# STeaMi-FP13-Port_Specifique.net
KiCad netlist of a schematic drawn in Altium Designer
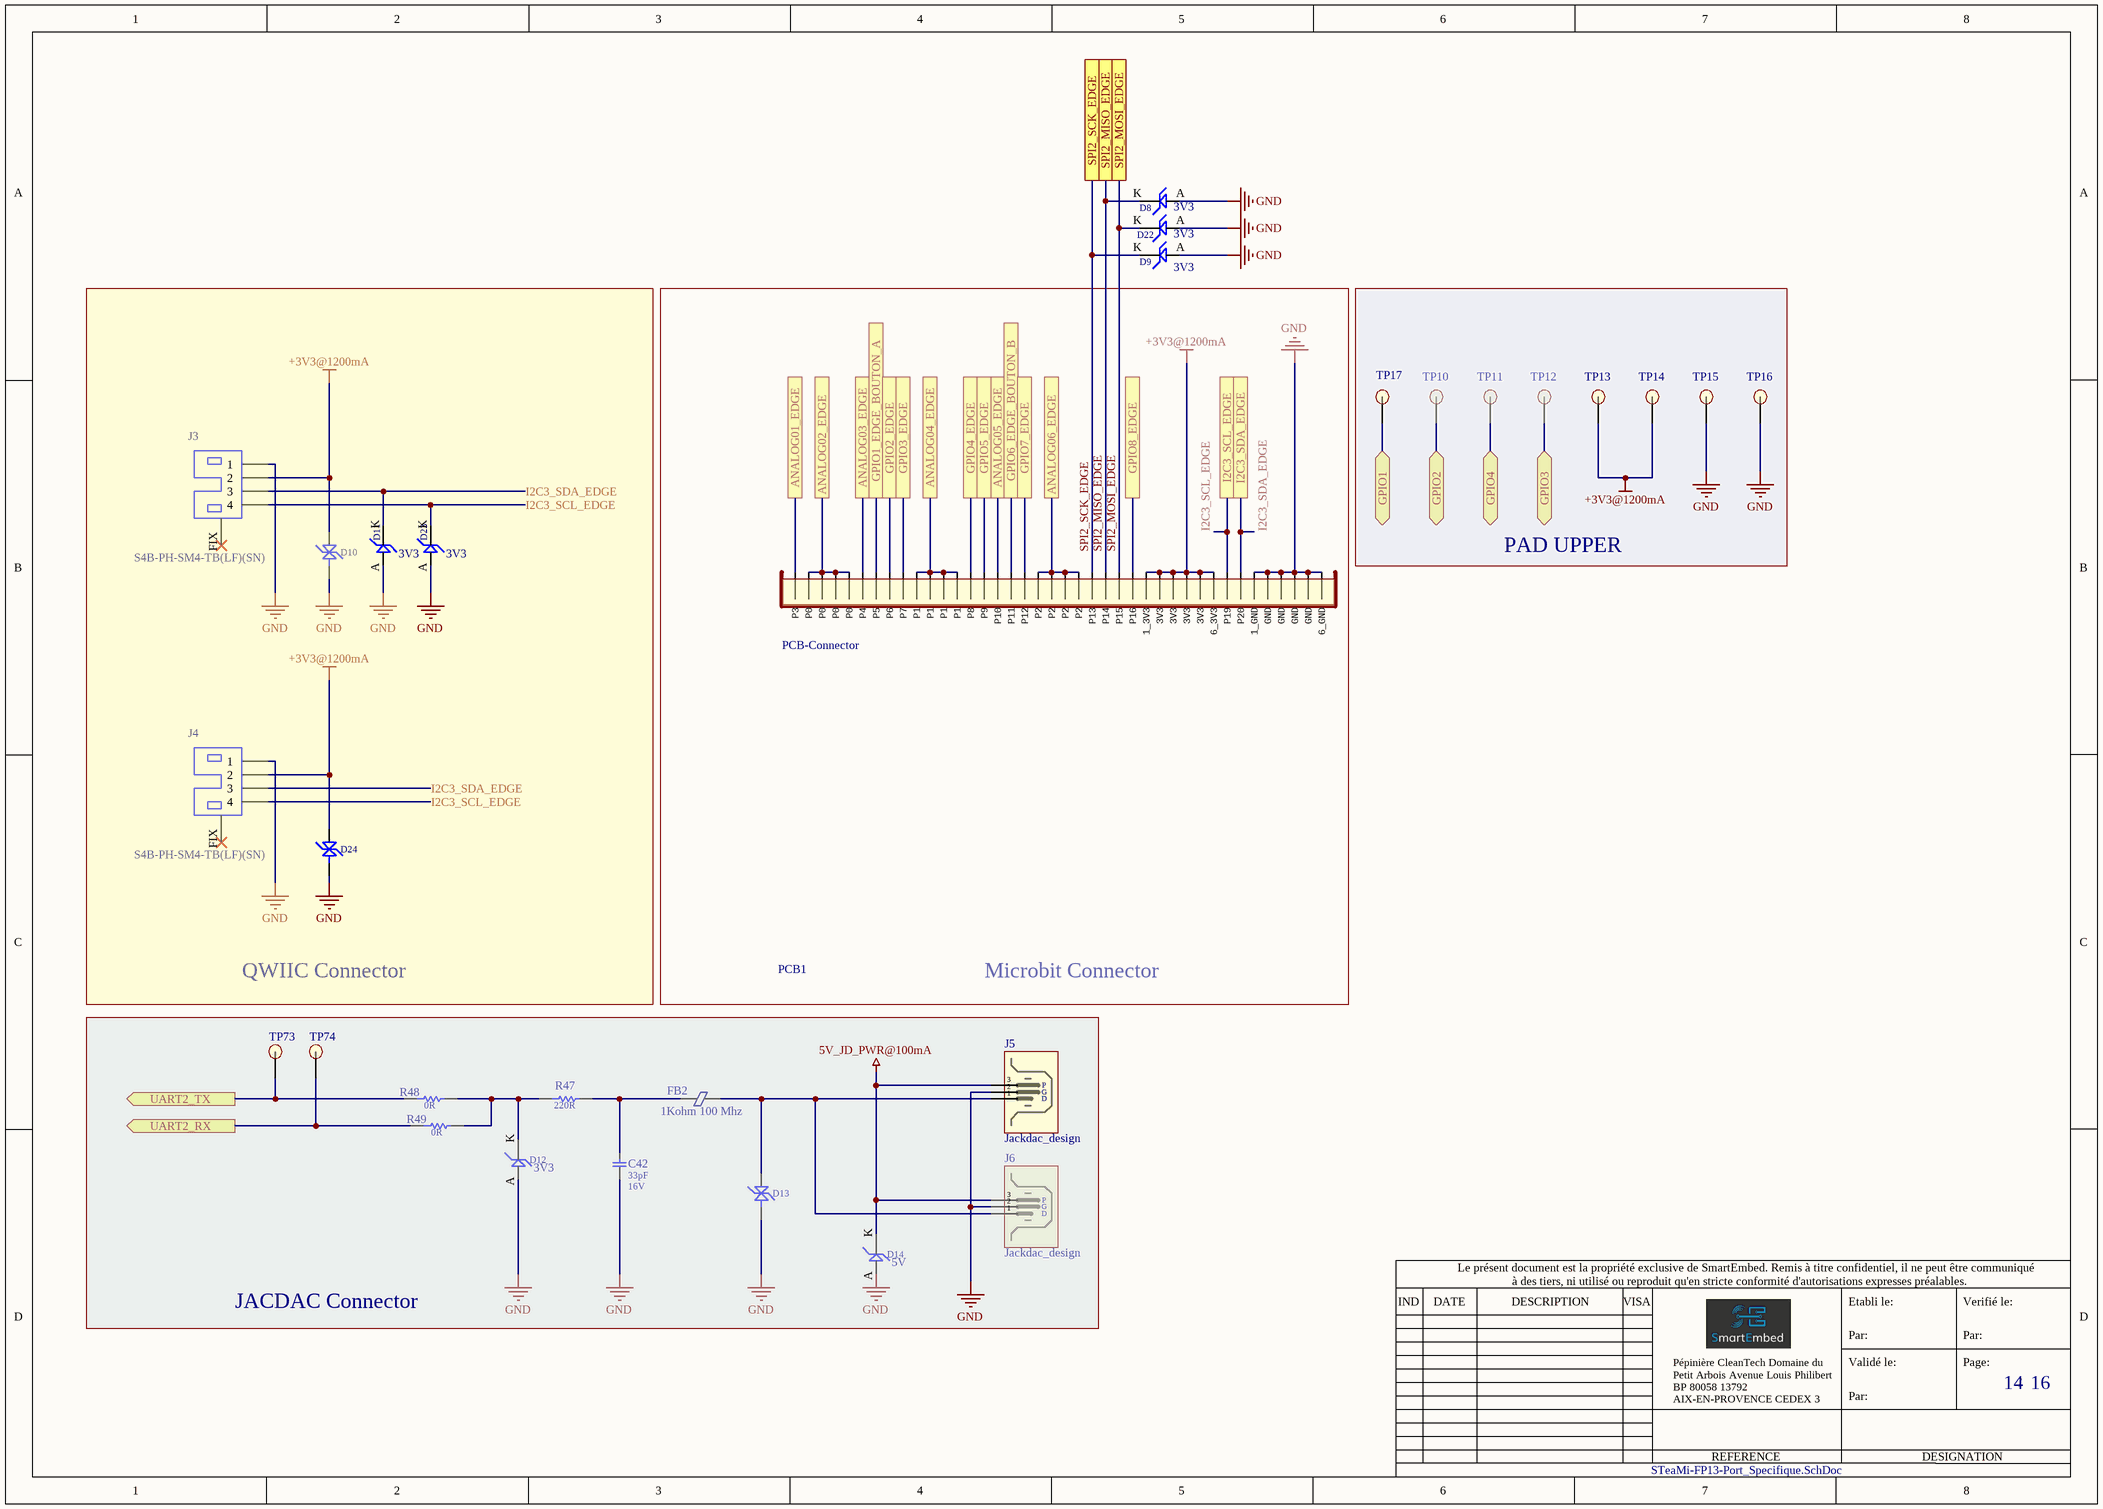
[diagram p0: STeaMi-FP13-Port_Specifique.SchDoc]

(export (version "E")
  (design (tool "Eeschema 10.0.6"))
  (components
    (comp (ref "C42")
      (value "~")
      (footprint "0402-CAP")
      (description "CAP CER 33pF 16V COG 0402")
      (fields
        (field (name "MANUFACTURER") "WURTH Electronics")
        (field (name "MANUFACTURER PART NUMBER") "885012005028")
        (field (name "CAPACITANCE") "33pF")
        (field (name "VOLTAGE") "16V")
        (field (name "CREATED BY") "EAG")
        (field (name "CHECKED BY") "*")
      )
      (libsource (lib "ComponentDB") (part "CAP_SYMBOL"))
    )
    (comp (ref "D8")
      (value "~")
      (footprint "SODFL1608X70N")
      (description "Suppresseurs ESD / diodes TVS LOW CAP SNAPBACK ESD PROT")
      (fields
        (field (name "MANUFACTURER") "OnSemiconductor")
        (field (name "MANUFACTURER PART NUMBER") "ESD8351XV2T1G")
        (field (name "VOLTAGE") "3V3")
        (field (name "CREATED BY") "EAG")
      )
      (libsource (lib "ComponentDB") (part "DIODE_ZENER_SYMBOL"))
    )
    (comp (ref "D9")
      (value "~")
      (footprint "SODFL1608X70N")
      (description "Suppresseurs ESD / diodes TVS LOW CAP SNAPBACK ESD PROT")
      (fields
        (field (name "MANUFACTURER") "OnSemiconductor")
        (field (name "MANUFACTURER PART NUMBER") "ESD8351XV2T1G")
        (field (name "VOLTAGE") "3V3")
        (field (name "CREATED BY") "EAG")
      )
      (libsource (lib "ComponentDB") (part "DIODE_ZENER_SYMBOL"))
    )
    (comp (ref "D10")
      (value "~")
      (footprint "DFN100X60X45-2N")
      (description "ESD Suppressors / TVS Diodes Transient Voltage Suppressor PP")
      (fields
        (field (name "MANUFACTURER") "Diodes Incorporated")
        (field (name "MANUFACTURER PART NUMBER") "D5V0H1B2LP-7B")
        (field (name "CREATED BY") "EAG")
      )
      (libsource (lib "ComponentDB") (part "SUPPRESSORS_DIODE"))
    )
    (comp (ref "D11")
      (value "~")
      (footprint "SODFL1608X70N")
      (description "Suppresseurs ESD / diodes TVS LOW CAP SNAPBACK ESD PROT")
      (fields
        (field (name "MANUFACTURER") "OnSemiconductor")
        (field (name "MANUFACTURER PART NUMBER") "ESD8351XV2T1G")
        (field (name "VOLTAGE") "3V3")
        (field (name "CREATED BY") "EAG")
      )
      (libsource (lib "ComponentDB") (part "DIODE_ZENER_SYMBOL"))
    )
    (comp (ref "D12")
      (value "~")
      (footprint "SODFL1608X70N")
      (description "Suppresseurs ESD / diodes TVS LOW CAP SNAPBACK ESD PROT")
      (fields
        (field (name "MANUFACTURER") "OnSemiconductor")
        (field (name "MANUFACTURER PART NUMBER") "ESD8351XV2T1G")
        (field (name "VOLTAGE") "3V3")
        (field (name "CREATED BY") "EAG")
      )
      (libsource (lib "ComponentDB") (part "DIODE_ZENER_SYMBOL"))
    )
    (comp (ref "D13")
      (value "~")
      (footprint "DFN100X60X45-2N")
      (description "ESD Suppressors / TVS Diodes Transient Voltage Suppressor PP")
      (fields
        (field (name "MANUFACTURER") "Diodes Incorporated")
        (field (name "MANUFACTURER PART NUMBER") "D5V0H1B2LP-7B")
        (field (name "CREATED BY") "EAG")
      )
      (libsource (lib "ComponentDB") (part "SUPPRESSORS_DIODE"))
    )
    (comp (ref "D14")
      (value "~")
      (footprint "SODFL1608X70N")
      (description "Suppresseurs ESD / diodes TVS LOW CAP SNAPBACK ESD PROT")
      (fields
        (field (name "MANUFACTURER") "OnSemiconductor")
        (field (name "MANUFACTURER PART NUMBER") "ESD8351XV2T1G")
        (field (name "VOLTAGE") "5V")
        (field (name "CREATED BY") "EAG")
      )
      (libsource (lib "ComponentDB") (part "DIODE_ZENER_SYMBOL"))
    )
    (comp (ref "D22")
      (value "~")
      (footprint "SODFL1608X70N")
      (description "Suppresseurs ESD / diodes TVS LOW CAP SNAPBACK ESD PROT")
      (fields
        (field (name "MANUFACTURER") "OnSemiconductor")
        (field (name "MANUFACTURER PART NUMBER") "ESD8351XV2T1G")
        (field (name "VOLTAGE") "3V3")
        (field (name "CREATED BY") "EAG")
      )
      (libsource (lib "ComponentDB") (part "DIODE_ZENER_SYMBOL"))
    )
    (comp (ref "D23")
      (value "~")
      (footprint "SODFL1608X70N")
      (description "Suppresseurs ESD / diodes TVS LOW CAP SNAPBACK ESD PROT")
      (fields
        (field (name "MANUFACTURER") "OnSemiconductor")
        (field (name "MANUFACTURER PART NUMBER") "ESD8351XV2T1G")
        (field (name "VOLTAGE") "3V3")
        (field (name "CREATED BY") "EAG")
      )
      (libsource (lib "ComponentDB") (part "DIODE_ZENER_SYMBOL"))
    )
    (comp (ref "D24")
      (value "~")
      (footprint "DFN100X60X45-2N")
      (description "ESD Suppressors / TVS Diodes Transient Voltage Suppressor PP")
      (fields
        (field (name "MANUFACTURER") "Diodes Incorporated")
        (field (name "MANUFACTURER PART NUMBER") "D5V0H1B2LP-7B")
        (field (name "CREATED BY") "EAG")
      )
      (libsource (lib "ComponentDB") (part "SUPPRESSORS_DIODE"))
    )
    (comp (ref "FB2")
      (value "1Kohm 100 Mhz")
      (footprint "BEADC1608X75N")
      (description "Chip Ferrite Bead 330 ohm à 100MHZ")
      (fields
        (field (name "MANUFACTURER") "MURATA")
        (field (name "MANUFACTURER PART NUMBER") "BLM18RK102SN1D")
        (field (name "CREATED BY") "EAG")
        (field (name "CHECKED BY") "*")
      )
      (libsource (lib "ComponentDB") (part "EMI_SYMBOL"))
    )
    (comp (ref "J3")
      (value "~")
      (footprint "JST_S4B-PH-SM4-TB")
      (description "Connecteur, embase Montage en surface à angle droit 4 positions (2,00mm)")
      (fields
        (field (name "MANUFACTURER") "JST")
        (field (name "MANUFACTURER PART NUMBER") "S4B-PH-SM4-TB(LF)(SN)")
        (field (name "PART NUMBER") "S4B-PH-SM4-TB(LF)(SN)")
        (field (name "CREATED BY") "EAG")
      )
      (libsource (lib "ComponentDB") (part "EMB_MALE_JST_PH_4PIN_1ROW_2MM_ANGLE_1"))
    )
    (comp (ref "J4")
      (value "~")
      (footprint "JST_S4B-PH-SM4-TB")
      (description "Connecteur, embase Montage en surface à angle droit 4 positions (2,00mm)")
      (fields
        (field (name "MANUFACTURER") "JST")
        (field (name "MANUFACTURER PART NUMBER") "S4B-PH-SM4-TB(LF)(SN)")
        (field (name "PART NUMBER") "S4B-PH-SM4-TB(LF)(SN)")
        (field (name "CREATED BY") "EAG")
      )
      (libsource (lib "ComponentDB") (part "EMB_MALE_JST_PH_4PIN_1ROW_2MM_ANGLE_1"))
    )
    (comp (ref "J5")
      (value "~")
      (footprint "JACDAC_FOOTPRINT")
      (description "PCB connector Jackdac")
      (fields
        (field (name "MANUFACTURER") "Microsoft")
        (field (name "MANUFACTURER PART NUMBER") "Jackdac_design")
        (field (name "PART NUMBER") "JACDAC_PCB")
        (field (name "CHECKED BY") "*")
        (field (name "CREATED BY") "EAG")
      )
      (libsource (lib "ComponentDB") (part "JACDAC_PCB"))
    )
    (comp (ref "J6")
      (value "~")
      (footprint "JACDAC_FOOTPRINT")
      (description "PCB connector Jackdac")
      (fields
        (field (name "MANUFACTURER") "Microsoft")
        (field (name "MANUFACTURER PART NUMBER") "Jackdac_design")
        (field (name "PART NUMBER") "JACDAC_PCB")
        (field (name "CHECKED BY") "*")
        (field (name "CREATED BY") "EAG")
      )
      (libsource (lib "ComponentDB") (part "JACDAC_PCB"))
    )
    (comp (ref "PCB1")
      (value "~")
      (footprint "MICROBIT_EDGE")
      (description "Design PCB connector P0-P16, 3V3,GND")
      (fields
        (field (name "MANUFACTURER") "MicroBit")
        (field (name "MANUFACTURER PART NUMBER") "PCB-Connector")
        (field (name "PART NUMBER") "PCBMICROBIT")
        (field (name "CREATED BY") "EAG")
        (field (name "CHECKED BY") "*")
      )
      (libsource (lib "ComponentDB") (part "PCBMICROBIT"))
    )
    (comp (ref "R47")
      (value "~")
      (footprint "RESC1005X40N_0402")
      (description "RES CMS 220R5%-0,1W-0402 ±10ppm/°C")
      (fields
        (field (name "MANUFACTURER") "Panasonic")
        (field (name "MANUFACTURER PART NUMBER") "ERJ-2GEJ221X")
        (field (name "RESISTANCE") "220R")
        (field (name "CREATED BY") "EAG")
      )
      (libsource (lib "ComponentDB") (part "RES_SYMBOL"))
    )
    (comp (ref "R48")
      (value "~")
      (footprint "RESC1005X40N_0402")
      (description "RES CMS 0R5%-0,0625W-0402")
      (fields
        (field (name "MANUFACTURER") "Yageo")
        (field (name "MANUFACTURER PART NUMBER") "RC0402JR-100RL")
        (field (name "RESISTANCE") "0R")
        (field (name "CREATED BY") "EAG")
      )
      (libsource (lib "ComponentDB") (part "RES_SYMBOL"))
    )
    (comp (ref "R49")
      (value "~")
      (footprint "RESC1005X40N_0402")
      (description "RES CMS 0R5%-0,0625W-0402")
      (fields
        (field (name "MANUFACTURER") "Yageo")
        (field (name "MANUFACTURER PART NUMBER") "RC0402JR-100RL")
        (field (name "RESISTANCE") "0R")
        (field (name "CREATED BY") "EAG")
      )
      (libsource (lib "ComponentDB") (part "RES_SYMBOL"))
    )
    (comp (ref "TP10")
      (value "PAD")
      (footprint "Pad_short_aligator")
      (description "Pad_short_aligator")
      (fields
        (field (name "MANUFACTURER") "Smartembed")
        (field (name "MANUFACTURER PART NUMBER") "ALIGATOR_TEST")
        (field (name "CREATED BY") "EAG")
      )
      (libsource (lib "ComponentDB") (part "TESTPOINT"))
    )
    (comp (ref "TP11")
      (value "PAD")
      (footprint "TEST:Pad_short_aligator")
      (description "Pad_short_aligator")
      (fields
        (field (name "MANUFACTURER") "Smartembed")
        (field (name "MANUFACTURER PART NUMBER") "ALIGATOR_TEST")
        (field (name "CREATED BY") "EAG")
      )
      (libsource (lib "ComponentDB") (part "TESTPOINT"))
    )
    (comp (ref "TP12")
      (value "PAD")
      (footprint "Pad_short_aligator")
      (description "Pad_short_aligator")
      (fields
        (field (name "MANUFACTURER") "Smartembed")
        (field (name "MANUFACTURER PART NUMBER") "ALIGATOR_TEST")
        (field (name "CREATED BY") "EAG")
      )
      (libsource (lib "ComponentDB") (part "TESTPOINT"))
    )
    (comp (ref "TP13")
      (value "PAD")
      (footprint "Pad_short_aligator")
      (description "Pad_short_aligator")
      (fields
        (field (name "MANUFACTURER") "Smartembed")
        (field (name "MANUFACTURER PART NUMBER") "ALIGATOR_TEST")
        (field (name "CREATED BY") "EAG")
      )
      (libsource (lib "ComponentDB") (part "TESTPOINT"))
    )
    (comp (ref "TP14")
      (value "PAD")
      (footprint "Pad_short_aligator")
      (description "Pad_short_aligator")
      (fields
        (field (name "MANUFACTURER") "Smartembed")
        (field (name "MANUFACTURER PART NUMBER") "ALIGATOR_TEST")
        (field (name "CREATED BY") "EAG")
      )
      (libsource (lib "ComponentDB") (part "TESTPOINT"))
    )
    (comp (ref "TP15")
      (value "PAD")
      (footprint "Pad_short_aligator")
      (description "Pad_short_aligator")
      (fields
        (field (name "MANUFACTURER") "Smartembed")
        (field (name "MANUFACTURER PART NUMBER") "ALIGATOR_TEST")
        (field (name "CREATED BY") "EAG")
      )
      (libsource (lib "ComponentDB") (part "TESTPOINT"))
    )
    (comp (ref "TP16")
      (value "PAD")
      (footprint "Pad_short_aligator")
      (description "Pad_short_aligator")
      (fields
        (field (name "MANUFACTURER") "Smartembed")
        (field (name "MANUFACTURER PART NUMBER") "ALIGATOR_TEST")
        (field (name "CREATED BY") "EAG")
      )
      (libsource (lib "ComponentDB") (part "TESTPOINT"))
    )
    (comp (ref "TP17")
      (value "PAD")
      (footprint "Pad_short_aligator")
      (description "Pad_short_aligator")
      (fields
        (field (name "MANUFACTURER") "Smartembed")
        (field (name "MANUFACTURER PART NUMBER") "ALIGATOR_TEST")
        (field (name "CREATED BY") "EAG")
      )
      (libsource (lib "ComponentDB") (part "TESTPOINT"))
    )
    (comp (ref "TP73")
      (value "TX2")
      (footprint "Testpoint 1mm")
      (description "TESTPOINTPAD")
      (fields (field (name "MANUFACTURER") "SmartEmbed"))
      (libsource (lib "ComponentDB") (part "TESTPOINT"))
    )
    (comp (ref "TP74")
      (value "RX2")
      (footprint "Testpoint 1mm")
      (description "TESTPOINTPAD")
      (fields (field (name "MANUFACTURER") "SmartEmbed"))
      (libsource (lib "ComponentDB") (part "TESTPOINT"))
    )
  )
  (nets
    (net (code "1") (name "+3V3@1200mA") (class "Default")
      (node (ref "D10") (pin "1") (pinfunction "A_1") (pintype "passive"))
      (node (ref "D24") (pin "1") (pinfunction "A_1") (pintype "passive"))
      (node (ref "J3") (pin "2") (pinfunction "2_2") (pintype "passive"))
      (node (ref "J4") (pin "2") (pinfunction "2_2") (pintype "passive"))
      (node (ref "PCB1") (pin "1_3V3") (pinfunction "1_3V3_1_3V3") (pintype "passive"))
      (node (ref "PCB1") (pin "3V3") (pinfunction "3V3_3V3") (pintype "passive"))
      (node (ref "PCB1") (pin "6_3V3") (pinfunction "6_3V3_6_3V3") (pintype "passive"))
      (node (ref "TP13") (pin "1") (pinfunction "1_1") (pintype "passive"))
      (node (ref "TP14") (pin "1") (pinfunction "1_1") (pintype "passive"))
    )
    (net (code "2") (name "/ANALOG01_EDGE") (class "Default")
      (node (ref "PCB1") (pin "P3") (pinfunction "P3_P3") (pintype "passive"))
    )
    (net (code "3") (name "/ANALOG02_EDGE") (class "Default")
      (node (ref "PCB1") (pin "P0") (pinfunction "P0_P0") (pintype "passive"))
    )
    (net (code "4") (name "/ANALOG03_EDGE") (class "Default")
      (node (ref "PCB1") (pin "P4") (pinfunction "P4_P4") (pintype "passive"))
    )
    (net (code "5") (name "/ANALOG04_EDGE") (class "Default")
      (node (ref "PCB1") (pin "P1") (pinfunction "P1_P1") (pintype "passive"))
    )
    (net (code "6") (name "/ANALOG05_EDGE") (class "Default")
      (node (ref "PCB1") (pin "P10") (pinfunction "P10_P10") (pintype "passive"))
    )
    (net (code "7") (name "/ANALOG06_EDGE") (class "Default")
      (node (ref "PCB1") (pin "P2") (pinfunction "P2_P2") (pintype "passive"))
    )
    (net (code "8") (name "/GPIO1") (class "Default")
      (node (ref "TP17") (pin "1") (pinfunction "1_1") (pintype "passive"))
    )
    (net (code "9") (name "/GPIO1_EDGE_BOUTON_A") (class "Default")
      (node (ref "PCB1") (pin "P5") (pinfunction "P5_P5") (pintype "passive"))
    )
    (net (code "10") (name "/GPIO2") (class "Default")
      (node (ref "TP10") (pin "1") (pinfunction "1_1") (pintype "passive"))
    )
    (net (code "11") (name "/GPIO2_EDGE") (class "Default")
      (node (ref "PCB1") (pin "P6") (pinfunction "P6_P6") (pintype "passive"))
    )
    (net (code "12") (name "/GPIO3") (class "Default")
      (node (ref "TP12") (pin "1") (pinfunction "1_1") (pintype "passive"))
    )
    (net (code "13") (name "/GPIO3_EDGE") (class "Default")
      (node (ref "PCB1") (pin "P7") (pinfunction "P7_P7") (pintype "passive"))
    )
    (net (code "14") (name "/GPIO4") (class "Default")
      (node (ref "TP11") (pin "1") (pinfunction "1_1") (pintype "passive"))
    )
    (net (code "15") (name "/GPIO4_EDGE") (class "Default")
      (node (ref "PCB1") (pin "P8") (pinfunction "P8_P8") (pintype "passive"))
    )
    (net (code "16") (name "/GPIO5_EDGE") (class "Default")
      (node (ref "PCB1") (pin "P9") (pinfunction "P9_P9") (pintype "passive"))
    )
    (net (code "17") (name "/GPIO6_EDGE_BOUTON_B") (class "Default")
      (node (ref "PCB1") (pin "P11") (pinfunction "P11_P11") (pintype "passive"))
    )
    (net (code "18") (name "/GPIO7_EDGE") (class "Default")
      (node (ref "PCB1") (pin "P12") (pinfunction "P12_P12") (pintype "passive"))
    )
    (net (code "19") (name "/GPIO8_EDGE") (class "Default")
      (node (ref "PCB1") (pin "P16") (pinfunction "P16_P16") (pintype "passive"))
    )
    (net (code "20") (name "/I2C3_SCL_EDGE") (class "Default")
      (node (ref "D23") (pin "K") (pinfunction "K_K") (pintype "passive"))
      (node (ref "J3") (pin "4") (pinfunction "4_4") (pintype "passive"))
      (node (ref "J4") (pin "4") (pinfunction "4_4") (pintype "passive"))
      (node (ref "PCB1") (pin "P19") (pinfunction "P19_P19") (pintype "passive"))
    )
    (net (code "21") (name "/I2C3_SDA_EDGE") (class "Default")
      (node (ref "D11") (pin "K") (pinfunction "K_K") (pintype "passive"))
      (node (ref "J3") (pin "3") (pinfunction "3_3") (pintype "passive"))
      (node (ref "J4") (pin "3") (pinfunction "3_3") (pintype "passive"))
      (node (ref "PCB1") (pin "P20") (pinfunction "P20_P20") (pintype "passive"))
    )
    (net (code "22") (name "/SPI2_MISO_EDGE") (class "Default")
      (node (ref "D8") (pin "K") (pinfunction "K_K") (pintype "passive"))
      (node (ref "PCB1") (pin "P14") (pinfunction "P14_P14") (pintype "passive"))
    )
    (net (code "23") (name "/SPI2_MOSI_EDGE") (class "Default")
      (node (ref "D22") (pin "K") (pinfunction "K_K") (pintype "passive"))
      (node (ref "PCB1") (pin "P15") (pinfunction "P15_P15") (pintype "passive"))
    )
    (net (code "24") (name "/SPI2_SCK_EDGE") (class "Default")
      (node (ref "D9") (pin "K") (pinfunction "K_K") (pintype "passive"))
      (node (ref "PCB1") (pin "P13") (pinfunction "P13_P13") (pintype "passive"))
    )
    (net (code "25") (name "/UART2_RX") (class "Default")
      (node (ref "R49") (pin "1") (pinfunction "1_1") (pintype "passive"))
      (node (ref "TP74") (pin "1") (pinfunction "1_1") (pintype "passive"))
    )
    (net (code "26") (name "/UART2_TX") (class "Default")
      (node (ref "R48") (pin "1") (pinfunction "1_1") (pintype "passive"))
      (node (ref "TP73") (pin "1") (pinfunction "1_1") (pintype "passive"))
    )
    (net (code "27") (name "5V_JD_PWR@100mA") (class "Default")
      (node (ref "D14") (pin "K") (pinfunction "K_K") (pintype "passive"))
      (node (ref "J5") (pin "3") (pinfunction "JD_PWR_3") (pintype "passive"))
      (node (ref "J6") (pin "3") (pinfunction "JD_PWR_3") (pintype "passive"))
    )
    (net (code "28") (name "GND") (class "Default")
      (node (ref "C42") (pin "1") (pinfunction "1_1") (pintype "passive"))
      (node (ref "D10") (pin "2") (pinfunction "K_2") (pintype "passive"))
      (node (ref "D11") (pin "A") (pinfunction "A_A") (pintype "passive"))
      (node (ref "D12") (pin "A") (pinfunction "A_A") (pintype "passive"))
      (node (ref "D13") (pin "2") (pinfunction "K_2") (pintype "passive"))
      (node (ref "D14") (pin "A") (pinfunction "A_A") (pintype "passive"))
      (node (ref "D22") (pin "A") (pinfunction "A_A") (pintype "passive"))
      (node (ref "D23") (pin "A") (pinfunction "A_A") (pintype "passive"))
      (node (ref "D24") (pin "2") (pinfunction "K_2") (pintype "passive"))
      (node (ref "D8") (pin "A") (pinfunction "A_A") (pintype "passive"))
      (node (ref "D9") (pin "A") (pinfunction "A_A") (pintype "passive"))
      (node (ref "J3") (pin "1") (pinfunction "1_1") (pintype "passive"))
      (node (ref "J4") (pin "1") (pinfunction "1_1") (pintype "passive"))
      (node (ref "J5") (pin "2") (pinfunction "GND_2") (pintype "passive"))
      (node (ref "J6") (pin "2") (pinfunction "GND_2") (pintype "passive"))
      (node (ref "PCB1") (pin "1_GND") (pinfunction "1_GND_1_GND") (pintype "passive"))
      (node (ref "PCB1") (pin "6_GND") (pinfunction "6_GND_6_GND") (pintype "passive"))
      (node (ref "PCB1") (pin "GND") (pinfunction "GND_GND") (pintype "passive"))
      (node (ref "TP15") (pin "1") (pinfunction "1_1") (pintype "passive"))
      (node (ref "TP16") (pin "1") (pinfunction "1_1") (pintype "passive"))
    )
    (net (code "29") (name "Net-(C42-Pad2)") (class "Default")
      (node (ref "C42") (pin "2") (pinfunction "2_2") (pintype "passive"))
      (node (ref "FB2") (pin "1") (pinfunction "1_1") (pintype "passive"))
      (node (ref "R47") (pin "2") (pinfunction "2_2") (pintype "passive"))
    )
    (net (code "30") (name "Net-(D12-PadK)") (class "Default")
      (node (ref "D12") (pin "K") (pinfunction "K_K") (pintype "passive"))
      (node (ref "R47") (pin "1") (pinfunction "1_1") (pintype "passive"))
      (node (ref "R48") (pin "2") (pinfunction "2_2") (pintype "passive"))
      (node (ref "R49") (pin "2") (pinfunction "2_2") (pintype "passive"))
    )
    (net (code "31") (name "Net-(D13-A)") (class "Default")
      (node (ref "D13") (pin "1") (pinfunction "A_1") (pintype "passive"))
      (node (ref "FB2") (pin "2") (pinfunction "2_2") (pintype "passive"))
      (node (ref "J5") (pin "1") (pinfunction "JD_DATA_1") (pintype "passive"))
      (node (ref "J6") (pin "1") (pinfunction "JD_DATA_1") (pintype "passive"))
    )
    (net (code "32") (name "unconnected-(J3-PadFIX)") (class "Default")
      (node (ref "J3") (pin "FIX") (pinfunction "FIX_FIX") (pintype "passive+no_connect"))
    )
    (net (code "33") (name "unconnected-(J4-PadFIX)") (class "Default")
      (node (ref "J4") (pin "FIX") (pinfunction "FIX_FIX") (pintype "passive+no_connect"))
    )
  )
)
